# LCD_-_Copy.net
KiCad netlist of a schematic drawn in Altium Designer
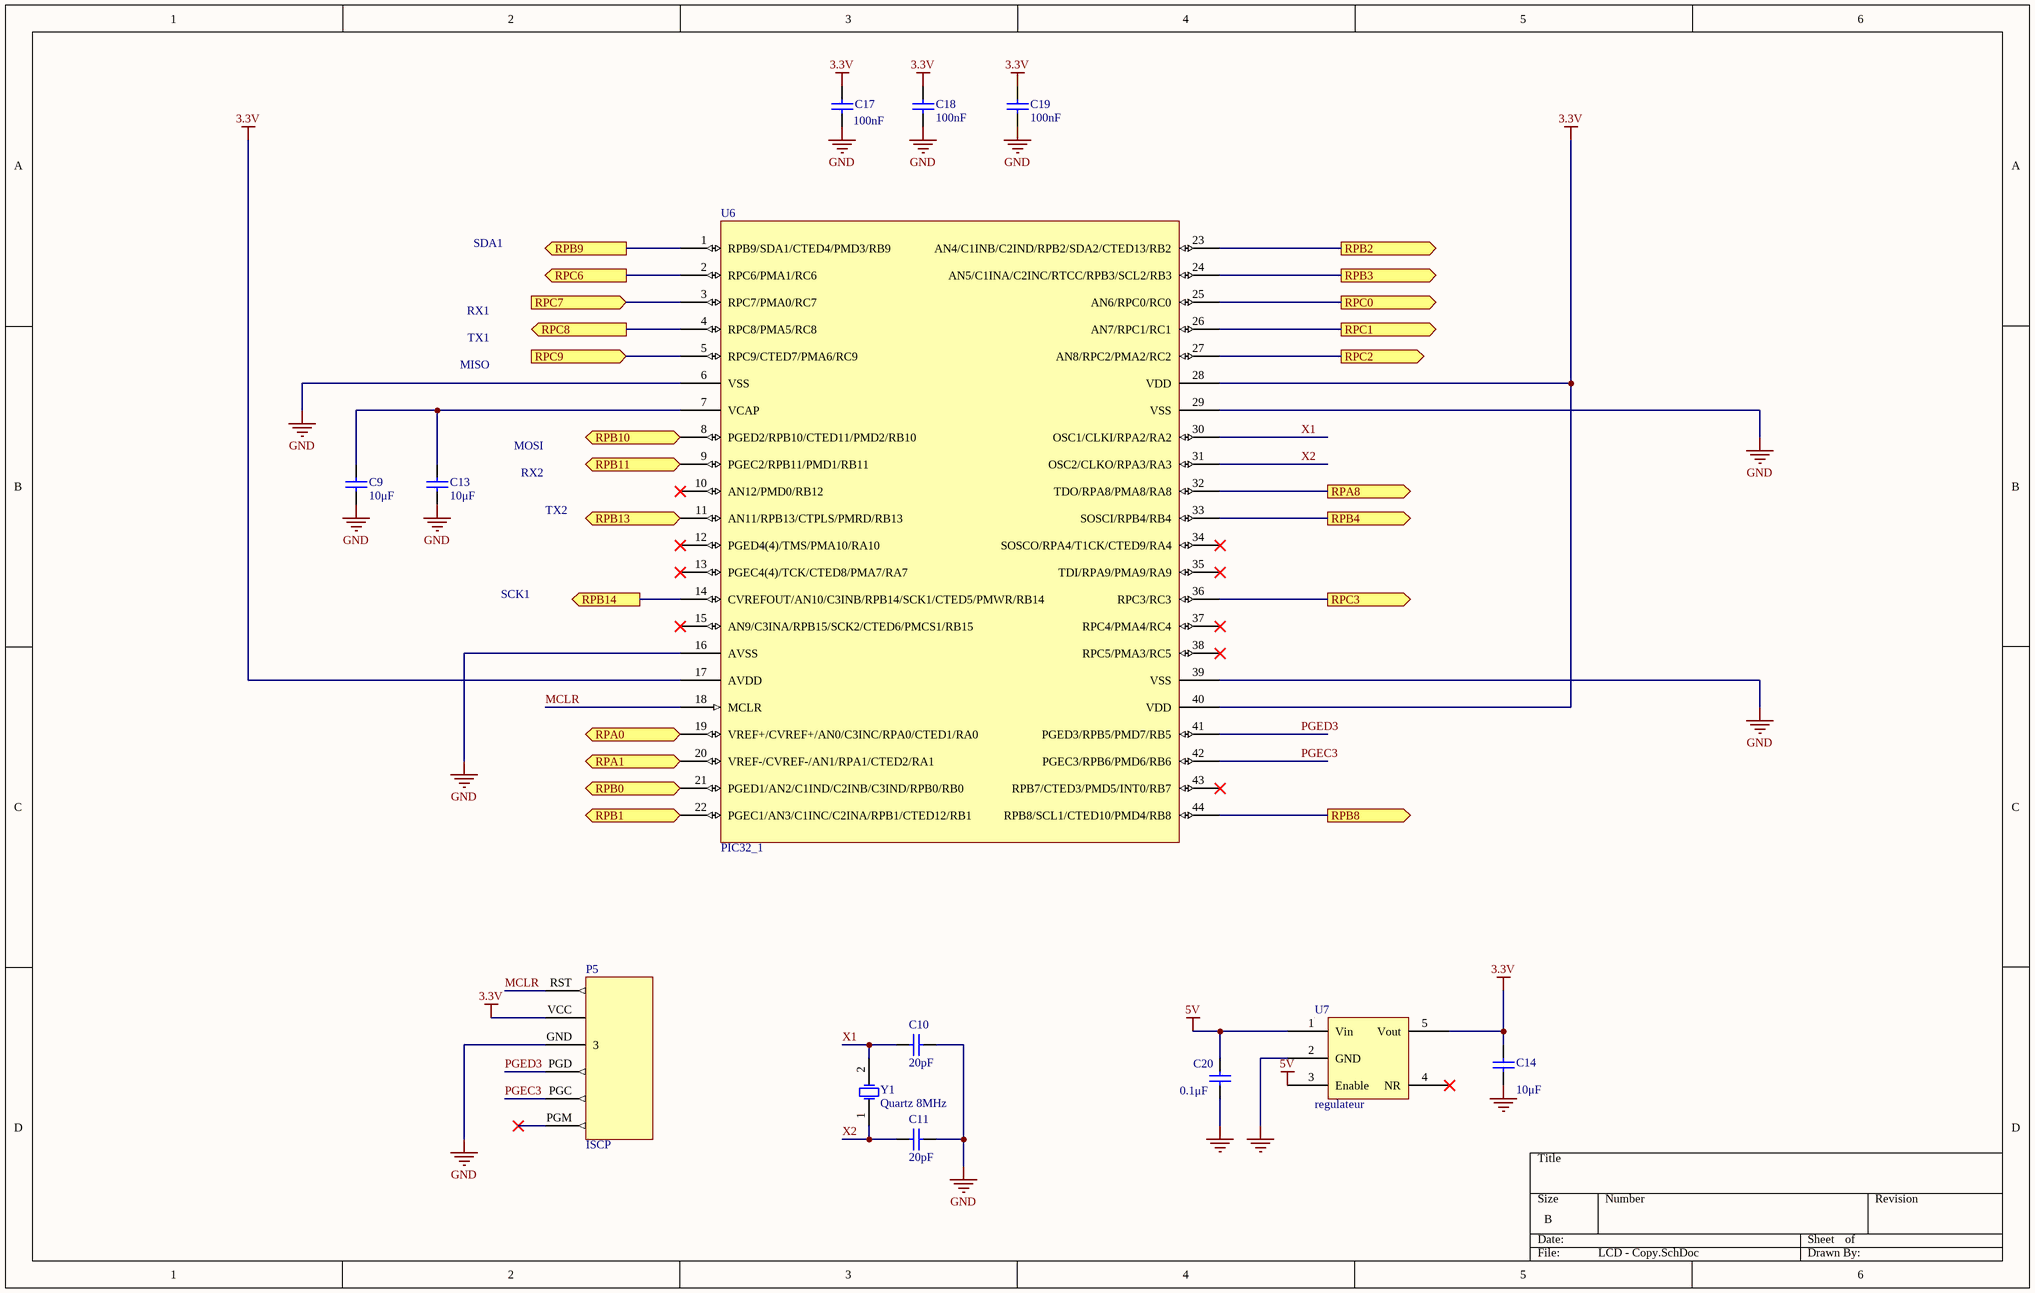
[diagram p0: LCD - Copy.SchDoc]

(export (version "E")
  (design (tool "Eeschema 10.0.6"))
  (components
    (comp (ref "C9")
      (value "10μF")
      (footprint "cond")
      (description "Capacitor")
      (fields (field (name "Comment") "Cap") (field (name "PUBLISHER") "Altium Limited"))
      (libsource (lib "Miscellaneous Devices") (part "Cap"))
    )
    (comp (ref "C10")
      (value "20pF")
      (footprint "cond")
      (description "Capacitor")
      (fields (field (name "Comment") "Cap") (field (name "PUBLISHER") "Altium Limited"))
      (libsource (lib "Miscellaneous Devices") (part "Cap"))
    )
    (comp (ref "C11")
      (value "20pF")
      (footprint "cond")
      (description "Capacitor")
      (fields (field (name "Comment") "Cap") (field (name "PUBLISHER") "Altium Limited"))
      (libsource (lib "Miscellaneous Devices") (part "Cap"))
    )
    (comp (ref "C13")
      (value "10μF")
      (footprint "cond")
      (description "Capacitor")
      (fields (field (name "Comment") "Cap") (field (name "PUBLISHER") "Altium Limited"))
      (libsource (lib "Miscellaneous Devices") (part "Cap"))
    )
    (comp (ref "C14")
      (value "10μF")
      (footprint "cond")
      (description "Capacitor")
      (fields (field (name "Comment") "Cap") (field (name "PUBLISHER") "Altium Limited"))
      (libsource (lib "Miscellaneous Devices") (part "Cap"))
    )
    (comp (ref "C17")
      (value "100nF")
      (footprint "cond")
      (description "Capacitor")
      (fields (field (name "Comment") "Cap") (field (name "PUBLISHER") "Altium Limited"))
      (libsource (lib "Miscellaneous Devices") (part "Cap"))
    )
    (comp (ref "C18")
      (value "100nF")
      (footprint "cond")
      (description "Capacitor")
      (fields (field (name "Comment") "Cap") (field (name "PUBLISHER") "Altium Limited"))
      (libsource (lib "Miscellaneous Devices") (part "Cap"))
    )
    (comp (ref "C19")
      (value "100nF")
      (footprint "cond")
      (description "Capacitor")
      (fields (field (name "Comment") "Cap") (field (name "PUBLISHER") "Altium Limited"))
      (libsource (lib "Miscellaneous Devices") (part "Cap"))
    )
    (comp (ref "C20")
      (value "0.1μF")
      (footprint "cond")
      (description "Capacitor")
      (fields (field (name "Comment") "Cap") (field (name "PUBLISHER") "Altium Limited"))
      (libsource (lib "Miscellaneous Devices") (part "Cap"))
    )
    (comp (ref "P5") (value "ISCP") (footprint "ISCP") (libsource (lib "Schlib1") (part "ISCP")))
    (comp (ref "U6") (value "PIC32_1") (libsource (lib "Schlib1") (part "PIC32_1")))
    (comp (ref "U7")
      (value "regulateur")
      (footprint "regulateur")
      (libsource (lib "Schlib1") (part "regulateur"))
    )
    (comp (ref "Y1")
      (value "Quartz 8MHz")
      (footprint "quartz")
      (description "Crystal Oscillator")
      (fields (field (name "PUBLISHER") "Altium Limited"))
      (libsource (lib "Miscellaneous Devices") (part "XTAL"))
    )
  )
  (nets
    (net (code "1") (name "/MCLR") (class "Default")
      (node (ref "P5") (pin "RST") (pinfunction "1_RST") (pintype "output"))
      (node (ref "U6") (pin "18") (pinfunction "MCLR_18") (pintype "input"))
    )
    (net (code "2") (name "/PGEC3") (class "Default")
      (node (ref "P5") (pin "PGC") (pinfunction "5_PGC") (pintype "output"))
      (node (ref "U6") (pin "42") (pinfunction "PGEC3/RPB6/PMD6/RB6_42") (pintype "bidirectional"))
    )
    (net (code "3") (name "/PGED3") (class "Default")
      (node (ref "P5") (pin "PGD") (pinfunction "4_PGD") (pintype "output"))
      (node (ref "U6") (pin "41") (pinfunction "PGED3/RPB5/PMD7/RB5_41") (pintype "bidirectional"))
    )
    (net (code "4") (name "/RPA0") (class "Default")
      (node (ref "U6") (pin "19") (pinfunction "VREF+/CVREF+/AN0/C3INC/RPA0/CTED1/RA0_19") (pintype "bidirectional"))
    )
    (net (code "5") (name "/RPA1") (class "Default")
      (node (ref "U6") (pin "20") (pinfunction "VREF-/CVREF-/AN1/RPA1/CTED2/RA1_20") (pintype "bidirectional"))
    )
    (net (code "6") (name "/RPA8") (class "Default")
      (node (ref "U6") (pin "32") (pinfunction "TDO/RPA8/PMA8/RA8_32") (pintype "bidirectional"))
    )
    (net (code "7") (name "/RPB0") (class "Default")
      (node (ref "U6") (pin "21") (pinfunction "PGED1/AN2/C1IND/C2INB/C3IND/RPB0/RB0_21") (pintype "bidirectional"))
    )
    (net (code "8") (name "/RPB1") (class "Default")
      (node (ref "U6") (pin "22") (pinfunction "PGEC1/AN3/C1INC/C2INA/RPB1/CTED12/RB1_22") (pintype "bidirectional"))
    )
    (net (code "9") (name "/RPB2") (class "Default")
      (node (ref "U6") (pin "23") (pinfunction "AN4/C1INB/C2IND/RPB2/SDA2/CTED13/RB2_23") (pintype "bidirectional"))
    )
    (net (code "10") (name "/RPB3") (class "Default")
      (node (ref "U6") (pin "24") (pinfunction "AN5/C1INA/C2INC/RTCC/RPB3/SCL2/RB3_24") (pintype "bidirectional"))
    )
    (net (code "11") (name "/RPB4") (class "Default")
      (node (ref "U6") (pin "33") (pinfunction "SOSCI/RPB4/RB4_33") (pintype "bidirectional"))
    )
    (net (code "12") (name "/RPB8") (class "Default")
      (node (ref "U6") (pin "44") (pinfunction "RPB8/SCL1/CTED10/PMD4/RB8_44") (pintype "bidirectional"))
    )
    (net (code "13") (name "/RPB9") (class "Default")
      (node (ref "U6") (pin "1") (pinfunction "RPB9/SDA1/CTED4/PMD3/RB9_1") (pintype "bidirectional"))
    )
    (net (code "14") (name "/RPB10") (class "Default")
      (node (ref "U6") (pin "8") (pinfunction "PGED2/RPB10/CTED11/PMD2/RB10_8") (pintype "bidirectional"))
    )
    (net (code "15") (name "/RPB11") (class "Default")
      (node (ref "U6") (pin "9") (pinfunction "PGEC2/RPB11/PMD1/RB11_9") (pintype "bidirectional"))
    )
    (net (code "16") (name "/RPB13") (class "Default")
      (node (ref "U6") (pin "11") (pinfunction "AN11/RPB13/CTPLS/PMRD/RB13_11") (pintype "bidirectional"))
    )
    (net (code "17") (name "/RPB14") (class "Default")
      (node (ref "U6") (pin "14") (pinfunction "CVREFOUT/AN10/C3INB/RPB14/SCK1/CTED5/PMWR/RB14_14") (pintype "bidirectional"))
    )
    (net (code "18") (name "/RPC0") (class "Default")
      (node (ref "U6") (pin "25") (pinfunction "AN6/RPC0/RC0_25") (pintype "bidirectional"))
    )
    (net (code "19") (name "/RPC1") (class "Default")
      (node (ref "U6") (pin "26") (pinfunction "AN7/RPC1/RC1_26") (pintype "bidirectional"))
    )
    (net (code "20") (name "/RPC2") (class "Default")
      (node (ref "U6") (pin "27") (pinfunction "AN8/RPC2/PMA2/RC2_27") (pintype "bidirectional"))
    )
    (net (code "21") (name "/RPC3") (class "Default")
      (node (ref "U6") (pin "36") (pinfunction "RPC3/RC3_36") (pintype "bidirectional"))
    )
    (net (code "22") (name "/RPC6") (class "Default")
      (node (ref "U6") (pin "2") (pinfunction "RPC6/PMA1/RC6_2") (pintype "bidirectional"))
    )
    (net (code "23") (name "/RPC7") (class "Default")
      (node (ref "U6") (pin "3") (pinfunction "RPC7/PMA0/RC7_3") (pintype "bidirectional"))
    )
    (net (code "24") (name "/RPC8") (class "Default")
      (node (ref "U6") (pin "4") (pinfunction "RPC8/PMA5/RC8_4") (pintype "bidirectional"))
    )
    (net (code "25") (name "/RPC9") (class "Default")
      (node (ref "U6") (pin "5") (pinfunction "RPC9/CTED7/PMA6/RC9_5") (pintype "bidirectional"))
    )
    (net (code "26") (name "/X1") (class "Default")
      (node (ref "C10") (pin "2") (pinfunction "2_2") (pintype "passive"))
      (node (ref "U6") (pin "30") (pinfunction "OSC1/CLKI/RPA2/RA2_30") (pintype "bidirectional"))
      (node (ref "Y1") (pin "2") (pinfunction "OSC2_2") (pintype "passive"))
    )
    (net (code "27") (name "/X2") (class "Default")
      (node (ref "C11") (pin "2") (pinfunction "2_2") (pintype "passive"))
      (node (ref "U6") (pin "31") (pinfunction "OSC2/CLKO/RPA3/RA3_31") (pintype "bidirectional"))
      (node (ref "Y1") (pin "1") (pinfunction "OSC1_1") (pintype "passive"))
    )
    (net (code "28") (name "3.3V") (class "Default")
      (node (ref "C14") (pin "2") (pinfunction "2_2") (pintype "passive"))
      (node (ref "C17") (pin "2") (pinfunction "2_2") (pintype "passive"))
      (node (ref "C18") (pin "1") (pinfunction "1_1") (pintype "passive"))
      (node (ref "C19") (pin "1") (pinfunction "1_1") (pintype "passive"))
      (node (ref "P5") (pin "VCC") (pinfunction "2_VCC") (pintype "passive"))
      (node (ref "U6") (pin "17") (pinfunction "AVDD_17") (pintype "passive"))
      (node (ref "U6") (pin "28") (pinfunction "VDD_28") (pintype "passive"))
      (node (ref "U6") (pin "40") (pinfunction "VDD_40") (pintype "passive"))
      (node (ref "U7") (pin "5") (pinfunction "Vout_5") (pintype "passive"))
    )
    (net (code "29") (name "5V") (class "Default")
      (node (ref "C20") (pin "2") (pinfunction "2_2") (pintype "passive"))
      (node (ref "U7") (pin "1") (pinfunction "Vin_1") (pintype "power_in"))
      (node (ref "U7") (pin "3") (pinfunction "Enable_3") (pintype "passive"))
    )
    (net (code "30") (name "GND") (class "Default")
      (node (ref "C10") (pin "1") (pinfunction "1_1") (pintype "passive"))
      (node (ref "C11") (pin "1") (pinfunction "1_1") (pintype "passive"))
      (node (ref "C13") (pin "2") (pinfunction "2_2") (pintype "passive"))
      (node (ref "C14") (pin "1") (pinfunction "1_1") (pintype "passive"))
      (node (ref "C17") (pin "1") (pinfunction "1_1") (pintype "passive"))
      (node (ref "C18") (pin "2") (pinfunction "2_2") (pintype "passive"))
      (node (ref "C19") (pin "2") (pinfunction "2_2") (pintype "passive"))
      (node (ref "C20") (pin "1") (pinfunction "1_1") (pintype "passive"))
      (node (ref "C9") (pin "2") (pinfunction "2_2") (pintype "passive"))
      (node (ref "P5") (pin "GND") (pinfunction "3_GND") (pintype "passive"))
      (node (ref "U6") (pin "16") (pinfunction "AVSS_16") (pintype "passive"))
      (node (ref "U6") (pin "29") (pinfunction "VSS_29") (pintype "power_in"))
      (node (ref "U6") (pin "39") (pinfunction "VSS_39") (pintype "power_in"))
      (node (ref "U6") (pin "6") (pinfunction "VSS_6") (pintype "passive"))
      (node (ref "U7") (pin "2") (pinfunction "GND_2") (pintype "passive"))
    )
    (net (code "31") (name "Net-(U6-VCAP)") (class "Default")
      (node (ref "C13") (pin "1") (pinfunction "1_1") (pintype "passive"))
      (node (ref "C9") (pin "1") (pinfunction "1_1") (pintype "passive"))
      (node (ref "U6") (pin "7") (pinfunction "VCAP_7") (pintype "passive"))
    )
    (net (code "32") (name "unconnected-(P5-6-PadPGM)") (class "Default")
      (node (ref "P5") (pin "PGM") (pinfunction "6_PGM") (pintype "output+no_connect"))
    )
    (net (code "33") (name "unconnected-(U6-AN9{slash}C3INA{slash}RPB15{slash}SCK2{slash}CTED6{slash}PMCS1{slash}RB15-Pad15)") (class "Default")
      (node (ref "U6") (pin "15") (pinfunction "AN9/C3INA/RPB15/SCK2/CTED6/PMCS1/RB15_15") (pintype "bidirectional+no_connect"))
    )
    (net (code "34") (name "unconnected-(U6-AN12{slash}PMD0{slash}RB12-Pad10)") (class "Default")
      (node (ref "U6") (pin "10") (pinfunction "AN12/PMD0/RB12_10") (pintype "bidirectional+no_connect"))
    )
    (net (code "35") (name "unconnected-(U6-PGEC4(4){slash}TCK{slash}CTED8{slash}PMA7{slash}RA7-Pad13)") (class "Default")
      (node (ref "U6") (pin "13") (pinfunction "PGEC4(4)/TCK/CTED8/PMA7/RA7_13") (pintype "bidirectional+no_connect"))
    )
    (net (code "36") (name "unconnected-(U6-PGED4(4){slash}TMS{slash}PMA10{slash}RA10-Pad12)") (class "Default")
      (node (ref "U6") (pin "12") (pinfunction "PGED4(4)/TMS/PMA10/RA10_12") (pintype "bidirectional+no_connect"))
    )
    (net (code "37") (name "unconnected-(U6-RPB7{slash}CTED3{slash}PMD5{slash}INT0{slash}RB7-Pad43)") (class "Default")
      (node (ref "U6") (pin "43") (pinfunction "RPB7/CTED3/PMD5/INT0/RB7_43") (pintype "bidirectional+no_connect"))
    )
    (net (code "38") (name "unconnected-(U6-RPC4{slash}PMA4{slash}RC4-Pad37)") (class "Default")
      (node (ref "U6") (pin "37") (pinfunction "RPC4/PMA4/RC4_37") (pintype "bidirectional+no_connect"))
    )
    (net (code "39") (name "unconnected-(U6-RPC5{slash}PMA3{slash}RC5-Pad38)") (class "Default")
      (node (ref "U6") (pin "38") (pinfunction "RPC5/PMA3/RC5_38") (pintype "bidirectional+no_connect"))
    )
    (net (code "40") (name "unconnected-(U6-SOSCO{slash}RPA4{slash}T1CK{slash}CTED9{slash}RA4-Pad34)") (class "Default")
      (node (ref "U6") (pin "34") (pinfunction "SOSCO/RPA4/T1CK/CTED9/RA4_34") (pintype "bidirectional+no_connect"))
    )
    (net (code "41") (name "unconnected-(U6-TDI{slash}RPA9{slash}PMA9{slash}RA9-Pad35)") (class "Default")
      (node (ref "U6") (pin "35") (pinfunction "TDI/RPA9/PMA9/RA9_35") (pintype "bidirectional+no_connect"))
    )
    (net (code "42") (name "unconnected-(U7-NR-Pad4)") (class "Default")
      (node (ref "U7") (pin "4") (pinfunction "NR_4") (pintype "passive+no_connect"))
    )
  )
)
